# MCU_PWR.net
KiCad netlist of a schematic drawn in Altium Designer
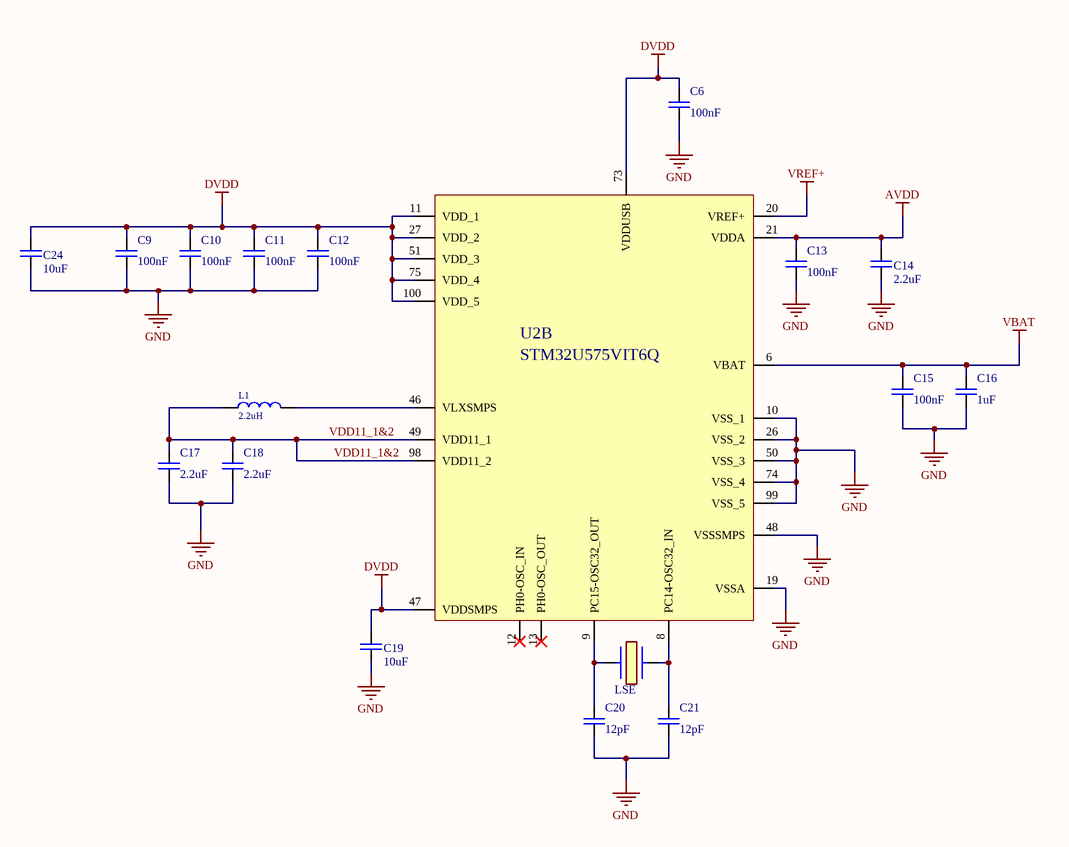
[diagram p0: MCU_PWR.SchDoc]

(export (version "E")
  (design (tool "Eeschema 10.0.6"))
  (components
    (comp (ref "C6")
      (value "100nF")
      (footprint "CAP_SM0805_YAGEOCC2_N")
      (description "CAP 100nF SM0805 X7R 50V YAGEO CC2")
      (fields
        (field (name "MANUFACTURER") "Yageo")
        (field (name "MANUFACTURER PART NUMBER") "CC0805KRX7R9BB104")
      )
      (libsource (lib "Yageo") (part "CC0805KRX7R9BB104"))
    )
    (comp (ref "C9")
      (value "100nF")
      (footprint "CAP_SM0805_YAGEOCC2_N")
      (description "CAP 100nF SM0805 X7R 50V YAGEO CC2")
      (fields
        (field (name "MANUFACTURER") "Yageo")
        (field (name "MANUFACTURER PART NUMBER") "CC0805KRX7R9BB104")
      )
      (libsource (lib "Yageo") (part "CC0805KRX7R9BB104"))
    )
    (comp (ref "C10")
      (value "100nF")
      (footprint "CAP_SM0805_YAGEOCC2_N")
      (description "CAP 100nF SM0805 X7R 50V YAGEO CC2")
      (fields
        (field (name "MANUFACTURER") "Yageo")
        (field (name "MANUFACTURER PART NUMBER") "CC0805KRX7R9BB104")
      )
      (libsource (lib "Yageo") (part "CC0805KRX7R9BB104"))
    )
    (comp (ref "C11")
      (value "100nF")
      (footprint "CAP_SM0805_YAGEOCC2_N")
      (description "CAP 100nF SM0805 X7R 50V YAGEO CC2")
      (fields
        (field (name "MANUFACTURER") "Yageo")
        (field (name "MANUFACTURER PART NUMBER") "CC0805KRX7R9BB104")
      )
      (libsource (lib "Yageo") (part "CC0805KRX7R9BB104"))
    )
    (comp (ref "C12")
      (value "100nF")
      (footprint "CAP_SM0805_YAGEOCC2_N")
      (description "CAP 100nF SM0805 X7R 50V YAGEO CC2")
      (fields
        (field (name "MANUFACTURER") "Yageo")
        (field (name "MANUFACTURER PART NUMBER") "CC0805KRX7R9BB104")
      )
      (libsource (lib "Yageo") (part "CC0805KRX7R9BB104"))
    )
    (comp (ref "C13")
      (value "100nF")
      (footprint "CAP_SM0805_YAGEOCC2_N")
      (description "CAP 100nF SM0805 X7R 50V YAGEO CC2")
      (fields
        (field (name "MANUFACTURER") "Yageo")
        (field (name "MANUFACTURER PART NUMBER") "CC0805KRX7R9BB104")
      )
      (libsource (lib "Yageo") (part "CC0805KRX7R9BB104"))
    )
    (comp (ref "C14")
      (value "2.2uF")
      (footprint "CAP_SM0805_YAGEOCC2_N")
      (description "CAP 2u2F SM0805 X7R 25V YAGEO CC2")
      (fields
        (field (name "MANUFACTURER") "Yageo")
        (field (name "MANUFACTURER PART NUMBER") "CC0805KKX7R8BB225")
      )
      (libsource (lib "Yageo") (part "CC0805KKX7R8BB225"))
    )
    (comp (ref "C15")
      (value "100nF")
      (footprint "CAP_SM0805_YAGEOCC2_N")
      (description "CAP 100nF SM0805 X7R 50V YAGEO CC2")
      (fields
        (field (name "MANUFACTURER") "Yageo")
        (field (name "MANUFACTURER PART NUMBER") "CC0805KRX7R9BB104")
      )
      (libsource (lib "Yageo") (part "CC0805KRX7R9BB104"))
    )
    (comp (ref "C16")
      (value "1uF")
      (footprint "CAP_SM0805_YAGEOCC2_N")
      (description "CAP 1uF SM0805 X7R 25V YAGEO CC2")
      (fields
        (field (name "MANUFACTURER") "Yageo")
        (field (name "MANUFACTURER PART NUMBER") "CC0805KKX7R8BB105")
      )
      (libsource (lib "Yageo") (part "CC0805KKX7R8BB105"))
    )
    (comp (ref "C17")
      (value "2.2uF")
      (footprint "CAP_SM0805_YAGEOCC2_N")
      (description "CAP 2u2F SM0805 X7R 25V YAGEO CC2")
      (fields
        (field (name "MANUFACTURER") "Yageo")
        (field (name "MANUFACTURER PART NUMBER") "CC0805KKX7R8BB225")
      )
      (libsource (lib "Yageo") (part "CC0805KKX7R8BB225"))
    )
    (comp (ref "C18")
      (value "2.2uF")
      (footprint "CAP_SM0805_YAGEOCC2_N")
      (description "CAP 2u2F SM0805 X7R 25V YAGEO CC2")
      (fields
        (field (name "MANUFACTURER") "Yageo")
        (field (name "MANUFACTURER PART NUMBER") "CC0805KKX7R8BB225")
      )
      (libsource (lib "Yageo") (part "CC0805KKX7R8BB225"))
    )
    (comp (ref "C19")
      (value "10uF")
      (footprint "CAP_SM0805_YAGEOCC2_N")
      (description "CAP 10uF SM0805 X5R 25V YAGEO")
      (fields
        (field (name "MANUFACTURER") "Yageo")
        (field (name "MANUFACTURER PART NUMBER") "CC0805KKX5R8BB106")
      )
      (libsource (lib "Yageo") (part "CC0805KKX5R8BB106"))
    )
    (comp (ref "C20")
      (value "12pF")
      (footprint "CAP_SM0805_YAGEOCC2_N")
      (description "CAP 12pF SM0805 NPO 50V YAGEO CC2")
      (fields
        (field (name "MANUFACTURER") "Yageo")
        (field (name "MANUFACTURER PART NUMBER") "CC0805JRNPO9BN120")
      )
      (libsource (lib "Yageo") (part "CC0805JRNPO9BN120"))
    )
    (comp (ref "C21")
      (value "12pF")
      (footprint "CAP_SM0805_YAGEOCC2_N")
      (description "CAP 12pF SM0805 NPO 50V YAGEO CC2")
      (fields
        (field (name "MANUFACTURER") "Yageo")
        (field (name "MANUFACTURER PART NUMBER") "CC0805JRNPO9BN120")
      )
      (libsource (lib "Yageo") (part "CC0805JRNPO9BN120"))
    )
    (comp (ref "C24")
      (value "10uF")
      (footprint "CAP_SM0805_YAGEOCC2_N")
      (description "CAP 10uF SM0805 X5R 25V YAGEO")
      (fields
        (field (name "MANUFACTURER") "Yageo")
        (field (name "MANUFACTURER PART NUMBER") "CC0805KKX5R8BB106")
      )
      (libsource (lib "Yageo") (part "CC0805KKX5R8BB106"))
    )
    (comp (ref "L1")
      (value "2.2uH")
      (footprint "LQM21PN2R2MGHL")
      (description "Inductores de potencia - SMD 2.2 UH 20%")
      (fields
        (field (name "MANUFACTURER") "Murata Electronics")
        (field (name "MANUFACTURER PART NUMBER") "LQM21PN2R2MGHL")
      )
      (libsource (lib "Inductores") (part "LQM21PN2R2MGHL"))
    )
    (comp (ref "LSE")
      (value "32,768 kHz")
      (footprint "SC-32S32.768kHz20PPM12.5pF")
      (description "Cristal Oscilador 32.768 kHz, 12.5pF")
      (fields
        (field (name "MANUFACTURER") "Seiko")
        (field (name "MANUFACTURER PART NUMBER") "SC32S-12.5PF20PPM")
      )
      (libsource (lib "Osciladores") (part "SC32S-12.5PF20PPM"))
    )
    (comp (ref "U2")
      (value "STM32U575VIT6Q")
      (footprint "STM32U575VI")
      (fields (field (name "MANUFACTURER") "ST"))
      (libsource (lib "Microcontroladores") (part "STM32U575VI_1"))
    )
  )
  (nets
    (net (code "1") (name "/VDD11_1&2") (class "Default")
      (node (ref "C17") (pin "1") (pintype "passive"))
      (node (ref "C18") (pin "1") (pintype "passive"))
      (node (ref "L1") (pin "1") (pinfunction "1_1") (pintype "passive"))
      (node (ref "U2") (pin "49") (pinfunction "VDD11_1_49") (pintype "passive"))
      (node (ref "U2") (pin "98") (pinfunction "VDD11_2_98") (pintype "passive"))
    )
    (net (code "2") (name "AVDD") (class "Default")
      (node (ref "C13") (pin "1") (pintype "passive"))
      (node (ref "C14") (pin "1") (pintype "passive"))
      (node (ref "U2") (pin "21") (pinfunction "VDDA_21") (pintype "passive"))
    )
    (net (code "3") (name "DVDD") (class "Default")
      (node (ref "C10") (pin "1") (pintype "passive"))
      (node (ref "C11") (pin "1") (pintype "passive"))
      (node (ref "C12") (pin "1") (pintype "passive"))
      (node (ref "C19") (pin "1") (pintype "passive"))
      (node (ref "C24") (pin "1") (pintype "passive"))
      (node (ref "C6") (pin "1") (pintype "passive"))
      (node (ref "C9") (pin "1") (pintype "passive"))
      (node (ref "U2") (pin "100") (pinfunction "VDD_5_100") (pintype "passive"))
      (node (ref "U2") (pin "11") (pinfunction "VDD_1_11") (pintype "passive"))
      (node (ref "U2") (pin "27") (pinfunction "VDD_2_27") (pintype "passive"))
      (node (ref "U2") (pin "47") (pinfunction "VDDSMPS_47") (pintype "passive"))
      (node (ref "U2") (pin "51") (pinfunction "VDD_3_51") (pintype "passive"))
      (node (ref "U2") (pin "73") (pinfunction "VDDUSB_73") (pintype "passive"))
      (node (ref "U2") (pin "75") (pinfunction "VDD_4_75") (pintype "passive"))
    )
    (net (code "4") (name "GND") (class "Default")
      (node (ref "C10") (pin "2") (pintype "passive"))
      (node (ref "C11") (pin "2") (pintype "passive"))
      (node (ref "C12") (pin "2") (pintype "passive"))
      (node (ref "C13") (pin "2") (pintype "passive"))
      (node (ref "C14") (pin "2") (pintype "passive"))
      (node (ref "C15") (pin "2") (pintype "passive"))
      (node (ref "C16") (pin "2") (pintype "passive"))
      (node (ref "C17") (pin "2") (pintype "passive"))
      (node (ref "C18") (pin "2") (pintype "passive"))
      (node (ref "C19") (pin "2") (pintype "passive"))
      (node (ref "C20") (pin "2") (pintype "passive"))
      (node (ref "C21") (pin "2") (pintype "passive"))
      (node (ref "C24") (pin "2") (pintype "passive"))
      (node (ref "C6") (pin "2") (pintype "passive"))
      (node (ref "C9") (pin "2") (pintype "passive"))
      (node (ref "U2") (pin "10") (pinfunction "VSS_1_10") (pintype "passive"))
      (node (ref "U2") (pin "19") (pinfunction "VSSA_19") (pintype "passive"))
      (node (ref "U2") (pin "26") (pinfunction "VSS_2_26") (pintype "passive"))
      (node (ref "U2") (pin "48") (pinfunction "VSSSMPS_48") (pintype "passive"))
      (node (ref "U2") (pin "50") (pinfunction "VSS_3_50") (pintype "passive"))
      (node (ref "U2") (pin "74") (pinfunction "VSS_4_74") (pintype "passive"))
      (node (ref "U2") (pin "99") (pinfunction "VSS_5_99") (pintype "passive"))
    )
    (net (code "5") (name "Net-(U2B-PC14-OSC32_IN)") (class "Default")
      (node (ref "C21") (pin "1") (pintype "passive"))
      (node (ref "LSE") (pin "2") (pinfunction "2_2") (pintype "passive"))
      (node (ref "U2") (pin "8") (pinfunction "PC14-OSC32_IN_8") (pintype "passive"))
    )
    (net (code "6") (name "Net-(U2B-PC15-OSC32_OUT)") (class "Default")
      (node (ref "C20") (pin "1") (pintype "passive"))
      (node (ref "LSE") (pin "1") (pinfunction "1_1") (pintype "passive"))
      (node (ref "U2") (pin "9") (pinfunction "PC15-OSC32_OUT_9") (pintype "passive"))
    )
    (net (code "7") (name "Net-(U2B-VLXSMPS)") (class "Default")
      (node (ref "L1") (pin "2") (pinfunction "2_2") (pintype "passive"))
      (node (ref "U2") (pin "46") (pinfunction "VLXSMPS_46") (pintype "passive"))
    )
    (net (code "8") (name "VBAT") (class "Default")
      (node (ref "C15") (pin "1") (pintype "passive"))
      (node (ref "C16") (pin "1") (pintype "passive"))
      (node (ref "U2") (pin "6") (pinfunction "VBAT_6") (pintype "passive"))
    )
    (net (code "9") (name "VREF+") (class "Default")
      (node (ref "U2") (pin "20") (pinfunction "VREF+_20") (pintype "passive"))
    )
    (net (code "10") (name "unconnected-(U2B-PH0-OSC_IN-Pad12)") (class "Default")
      (node (ref "U2") (pin "12") (pinfunction "PH0-OSC_IN_12") (pintype "passive+no_connect"))
    )
    (net (code "11") (name "unconnected-(U2B-PH0-OSC_OUT-Pad13)") (class "Default")
      (node (ref "U2") (pin "13") (pinfunction "PH0-OSC_OUT_13") (pintype "passive+no_connect"))
    )
  )
)
